# Self-Oscillating_Converter.net
KiCad netlist of a schematic drawn in Altium Designer
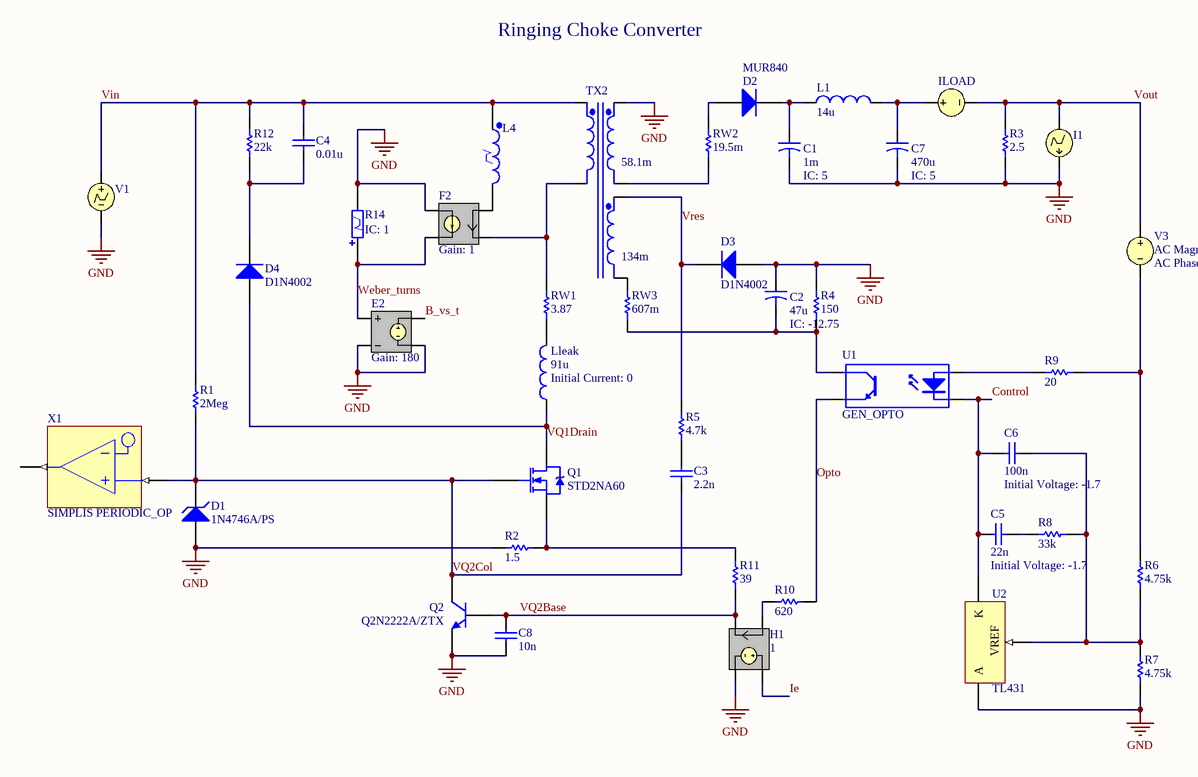
[diagram p0: Self-Oscillating Converter.SchDoc]

(export (version "E")
  (design (tool "Eeschema 10.0.6"))
  (components
    (comp (ref "C1")
      (value "Cap Elec (L1-3)")
      (footprint "CAPR5-4X5")
      (description "Electrolytic Capacitor (Levels 1-3)")
      (fields (field (name "IC") "5") (field (name "CC") "1m") (field (name "PUBLISHER") "Altium Limited"))
      (libsource (lib "SIMetrix Devices") (part "Cap Elec (L1-3)"))
    )
    (comp (ref "C2")
      (value "Cap Elec (L1-3)")
      (footprint "CAPR5-4X5")
      (description "Electrolytic Capacitor (Levels 1-3)")
      (fields
        (field (name "IC") "-12.75")
        (field (name "CC") "47u")
        (field (name "PUBLISHER") "Altium Limited")
      )
      (libsource (lib "SIMetrix Devices") (part "Cap Elec (L1-3)"))
    )
    (comp (ref "C3")
      (value "2.2n")
      (footprint "RAD-0.3")
      (description "Capacitor")
      (fields (field (name "Comment") "Cap") (field (name "PUBLISHER") "Altium Limited"))
      (libsource (lib "Miscellaneous Devices") (part "Cap"))
    )
    (comp (ref "C4")
      (value "0.01u")
      (footprint "RAD-0.3")
      (description "Capacitor")
      (fields (field (name "Comment") "Cap") (field (name "PUBLISHER") "Altium Limited"))
      (libsource (lib "Miscellaneous Devices") (part "Cap"))
    )
    (comp (ref "C5")
      (value "22n")
      (footprint "RAD-0.3")
      (description "Capacitor")
      (fields
        (field (name "INITIAL VOLTAGE") "-1.7")
        (field (name "Comment") "Cap")
        (field (name "PUBLISHER") "Altium Limited")
      )
      (libsource (lib "Miscellaneous Devices") (part "Cap"))
    )
    (comp (ref "C6")
      (value "100n")
      (footprint "RAD-0.3")
      (description "Capacitor")
      (fields
        (field (name "INITIAL VOLTAGE") "-1.7")
        (field (name "Comment") "Cap")
        (field (name "PUBLISHER") "Altium Limited")
      )
      (libsource (lib "Miscellaneous Devices") (part "Cap"))
    )
    (comp (ref "C7")
      (value "Cap Elec (L1-3)")
      (footprint "CAPR5-4X5")
      (description "Electrolytic Capacitor (Levels 1-3)")
      (fields (field (name "IC") "5") (field (name "CC") "470u") (field (name "PUBLISHER") "Altium Limited"))
      (libsource (lib "SIMetrix Devices") (part "Cap Elec (L1-3)"))
    )
    (comp (ref "C8")
      (value "10n")
      (footprint "RAD-0.3")
      (description "Capacitor")
      (fields (field (name "Comment") "Cap") (field (name "PUBLISHER") "Altium Limited"))
      (libsource (lib "Miscellaneous Devices") (part "Cap"))
    )
    (comp (ref "D1")
      (value "1N4746A/PS")
      (footprint "59-03")
      (description "One Watt Hermetically Sealed Glass Silicon Zener Diode")
      (fields (field (name "PUBLISHER") "Altium Limited"))
      (libsource (lib "SIMetrix Devices") (part "1N4746A/PS"))
    )
    (comp (ref "D2")
      (value "MUR840")
      (footprint "SMC")
      (description "Ultrafast Recovery Rectifier")
      (fields (field (name "PUBLISHER") "Altium Limited"))
      (libsource (lib "SIMetrix Devices") (part "MUR840"))
    )
    (comp (ref "D3")
      (value "D1N4002")
      (footprint "DO-41")
      (description "1 Amp General Purpose Rectifier")
      (fields (field (name "PUBLISHER") "Altium Limited"))
      (libsource (lib "SIMetrix Devices") (part "D1N4002"))
    )
    (comp (ref "D4")
      (value "D1N4002")
      (footprint "DO-41")
      (description "1 Amp General Purpose Rectifier")
      (fields (field (name "PUBLISHER") "Altium Limited"))
      (libsource (lib "SIMetrix Devices") (part "D1N4002"))
    )
    (comp (ref "E2")
      (value "ESRC")
      (description "Voltage Controlled Voltage Source")
      (fields (field (name "GAIN") "180") (field (name "PUBLISHER") "Altium Limited"))
      (libsource (lib "Simulation Sources") (part "ESRC"))
    )
    (comp (ref "F2")
      (value "FSRC")
      (description "Current Controlled Current Source")
      (fields (field (name "GAIN") "1") (field (name "PUBLISHER") "Altium Limited"))
      (libsource (lib "Simulation Sources") (part "FSRC"))
    )
    (comp (ref "H1")
      (value "HSRC")
      (description "Current Controlled Voltage Source")
      (fields (field (name "GAIN") "1") (field (name "PUBLISHER") "Altium Limited"))
      (libsource (lib "Simulation Sources") (part "HSRC"))
    )
    (comp (ref "I1")
      (value "IPWL")
      (description "Piecewise Linear Current Source")
      (fields (field (name "PUBLISHER") "Altium Limited"))
      (libsource (lib "Simulation Sources") (part "IPWL"))
    )
    (comp (ref "ILOAD")
      (value "VSRC")
      (description "Voltage Source")
      (fields (field (name "PUBLISHER") "Altium Limited"))
      (libsource (lib "Simulation Sources") (part "VSRC"))
    )
    (comp (ref "L1")
      (value "14u")
      (footprint "0402-A")
      (description "Lossy Inductor")
      (fields (field (name "PUBLISHER") "Altium Limited"))
      (libsource (lib "SIMetrix Devices") (part "Inductor (Lossy)"))
    )
    (comp (ref "L4")
      (value "SIMPLIS PWLL5")
      (description "Piecewise Linear Inductor (5-segment)")
      (fields (field (name "PUBLISHER") "Altium Limited"))
      (libsource (lib "SIMPLIS Devices") (part "SIMPLIS PWLL5"))
    )
    (comp (ref "Lleak")
      (value "91u")
      (footprint "0402-A")
      (description "Inductor")
      (fields (field (name "INITIAL CURRENT") "0") (field (name "PUBLISHER") "Altium Limited"))
      (libsource (lib "Miscellaneous Devices") (part "Inductor"))
    )
    (comp (ref "Q1")
      (value "STD2NA60")
      (footprint "TO-220AB")
      (description "N-Channel Enhancement Mode Power MOS Transistor")
      (fields (field (name "PUBLISHER") "Altium Limited"))
      (libsource (lib "SIMetrix Devices") (part "STD2NA60"))
    )
    (comp (ref "Q2")
      (value "Q2N2222A/ZTX")
      (footprint "TO-18")
      (description "Zetex General Purpose Transistor NPN Silicon")
      (fields (field (name "PUBLISHER") "Altium Limited"))
      (libsource (lib "SIMetrix Devices") (part "Q2N2222A/ZTX"))
    )
    (comp (ref "R1")
      (value "2Meg")
      (footprint "AXIAL-0.3")
      (description "Resistor")
      (fields (field (name "Comment") "Res1") (field (name "PUBLISHER") "Altium Limited"))
      (libsource (lib "Miscellaneous Devices") (part "Res1"))
    )
    (comp (ref "R2")
      (value "1.5")
      (footprint "AXIAL-0.3")
      (description "Resistor")
      (fields (field (name "Comment") "Res1") (field (name "PUBLISHER") "Altium Limited"))
      (libsource (lib "Miscellaneous Devices") (part "Res1"))
    )
    (comp (ref "R3")
      (value "2.5")
      (footprint "AXIAL-0.3")
      (description "Resistor")
      (fields (field (name "Comment") "Res1") (field (name "PUBLISHER") "Altium Limited"))
      (libsource (lib "Miscellaneous Devices") (part "Res1"))
    )
    (comp (ref "R4")
      (value "150")
      (footprint "AXIAL-0.3")
      (description "Resistor")
      (fields (field (name "Comment") "Res1") (field (name "PUBLISHER") "Altium Limited"))
      (libsource (lib "Miscellaneous Devices") (part "Res1"))
    )
    (comp (ref "R5")
      (value "4.7k")
      (footprint "AXIAL-0.3")
      (description "Resistor")
      (fields (field (name "Comment") "Res1") (field (name "PUBLISHER") "Altium Limited"))
      (libsource (lib "Miscellaneous Devices") (part "Res1"))
    )
    (comp (ref "R6")
      (value "4.75k")
      (footprint "AXIAL-0.3")
      (description "Resistor")
      (fields (field (name "Comment") "Res1") (field (name "PUBLISHER") "Altium Limited"))
      (libsource (lib "Miscellaneous Devices") (part "Res1"))
    )
    (comp (ref "R7")
      (value "4.75k")
      (footprint "AXIAL-0.3")
      (description "Resistor")
      (fields (field (name "Comment") "Res1") (field (name "PUBLISHER") "Altium Limited"))
      (libsource (lib "Miscellaneous Devices") (part "Res1"))
    )
    (comp (ref "R8")
      (value "33k")
      (footprint "AXIAL-0.3")
      (description "Resistor")
      (fields (field (name "Comment") "Res1") (field (name "PUBLISHER") "Altium Limited"))
      (libsource (lib "Miscellaneous Devices") (part "Res1"))
    )
    (comp (ref "R9")
      (value "20")
      (footprint "AXIAL-0.3")
      (description "Resistor")
      (fields (field (name "Comment") "Res1") (field (name "PUBLISHER") "Altium Limited"))
      (libsource (lib "Miscellaneous Devices") (part "Res1"))
    )
    (comp (ref "R10")
      (value "620")
      (footprint "AXIAL-0.3")
      (description "Resistor")
      (fields (field (name "Comment") "Res1") (field (name "PUBLISHER") "Altium Limited"))
      (libsource (lib "Miscellaneous Devices") (part "Res1"))
    )
    (comp (ref "R11")
      (value "39")
      (footprint "AXIAL-0.3")
      (description "Resistor")
      (fields (field (name "Comment") "Res1") (field (name "PUBLISHER") "Altium Limited"))
      (libsource (lib "Miscellaneous Devices") (part "Res1"))
    )
    (comp (ref "R12")
      (value "22k")
      (footprint "AXIAL-0.3")
      (description "Resistor")
      (fields (field (name "Comment") "Res1") (field (name "PUBLISHER") "Altium Limited"))
      (libsource (lib "Miscellaneous Devices") (part "Res1"))
    )
    (comp (ref "R14")
      (value "SIMPLIS VPWLR5")
      (description "Voltage-Controlled Piecewise Linear Resistor (5-segment)")
      (fields (field (name "IC") "1") (field (name "PUBLISHER") "Altium Limited"))
      (libsource (lib "SIMPLIS Devices") (part "SIMPLIS VPWLR5"))
    )
    (comp (ref "RW1")
      (value "3.87")
      (footprint "AXIAL-0.3")
      (description "Resistor")
      (fields (field (name "Comment") "Res1") (field (name "PUBLISHER") "Altium Limited"))
      (libsource (lib "Miscellaneous Devices") (part "Res1"))
    )
    (comp (ref "RW2")
      (value "19.5m")
      (footprint "AXIAL-0.3")
      (description "Resistor")
      (fields (field (name "Comment") "Res1") (field (name "PUBLISHER") "Altium Limited"))
      (libsource (lib "Miscellaneous Devices") (part "Res1"))
    )
    (comp (ref "RW3")
      (value "607m")
      (footprint "AXIAL-0.3")
      (description "Resistor")
      (fields (field (name "Comment") "Res1") (field (name "PUBLISHER") "Altium Limited"))
      (libsource (lib "Miscellaneous Devices") (part "Res1"))
    )
    (comp (ref "TX2")
      (value "Trans3 Ideal")
      (footprint "TRF_6")
      (description "Three-winding Transformer (Ideal)")
      (fields
        (field (name "RATIO1") "58.1m")
        (field (name "RATIO2") "134m")
        (field (name "PUBLISHER") "Altium Limited")
      )
      (libsource (lib "Miscellaneous Devices") (part "Trans3 Ideal"))
    )
    (comp (ref "U1")
      (value "GEN_OPTO")
      (footprint "DIP-4")
      (description "General-Purpose Optocoupler")
      (fields (field (name "PUBLISHER") "Altium Limited"))
      (libsource (lib "SIMetrix Devices") (part "GEN_OPTO"))
    )
    (comp (ref "U2")
      (value "TL431")
      (footprint "LP03")
      (description "Adjustable Precision Shunt Regulator")
      (fields (field (name "PUBLISHER") "Altium Limited"))
      (libsource (lib "SIMetrix Devices") (part "TL431"))
    )
    (comp (ref "V1")
      (value "VPWL")
      (description "Piecewise Linear Voltage Source")
      (fields (field (name "PUBLISHER") "Altium Limited"))
      (libsource (lib "Simulation Sources") (part "VPWL"))
    )
    (comp (ref "V3")
      (value "VSRC")
      (description "Voltage Source")
      (fields
        (field (name "AC MAGNITUDE") "1")
        (field (name "AC PHASE") "0")
        (field (name "PUBLISHER") "Altium Limited")
      )
      (libsource (lib "Simulation Sources") (part "VSRC"))
    )
    (comp (ref "X1")
      (value "SIMPLIS PERIODIC_OP")
      (description "Periodic Operating Point Analysis Trigger")
      (fields (field (name "PUBLISHER") "Altium Limited"))
      (libsource (lib "SIMPLIS Devices") (part "SIMPLIS PERIODIC_OP"))
    )
  )
  (nets
    (net (code "1") (name "/B_vs_t") (class "Default")
      (node (ref "E2") (pin "3") (pinfunction "N+_3") (pintype "passive"))
    )
    (net (code "2") (name "/Control") (class "Default")
      (node (ref "C5") (pin "2") (pinfunction "2_2") (pintype "passive"))
      (node (ref "C6") (pin "2") (pinfunction "2_2") (pintype "passive"))
      (node (ref "U1") (pin "2") (pinfunction "K_2") (pintype "passive"))
      (node (ref "U2") (pin "3") (pinfunction "K_3") (pintype "power_in"))
    )
    (net (code "3") (name "/Ie") (class "Default")
      (node (ref "H1") (pin "3") (pinfunction "N+_3") (pintype "passive"))
    )
    (net (code "4") (name "/Opto") (class "Default")
      (node (ref "R10") (pin "1") (pinfunction "1_1") (pintype "passive"))
      (node (ref "U1") (pin "3") (pinfunction "E_3") (pintype "passive"))
    )
    (net (code "5") (name "/VQ1Drain") (class "Default")
      (node (ref "D4") (pin "1") (pinfunction "A_1") (pintype "passive"))
      (node (ref "Lleak") (pin "1") (pinfunction "1_1") (pintype "passive"))
      (node (ref "Q1") (pin "2") (pinfunction "D_2") (pintype "passive"))
    )
    (net (code "6") (name "/VQ2Base") (class "Default")
      (node (ref "C8") (pin "1") (pinfunction "1_1") (pintype "passive"))
      (node (ref "H1") (pin "2") (pinfunction "NC-_2") (pintype "passive"))
      (node (ref "Q2") (pin "2") (pinfunction "B_2") (pintype "passive"))
      (node (ref "R11") (pin "1") (pinfunction "1_1") (pintype "passive"))
    )
    (net (code "7") (name "/VQ2Col") (class "Default")
      (node (ref "C3") (pin "1") (pinfunction "1_1") (pintype "passive"))
      (node (ref "D1") (pin "2") (pinfunction "K_2") (pintype "passive"))
      (node (ref "Q1") (pin "1") (pinfunction "G_1") (pintype "passive"))
      (node (ref "Q2") (pin "3") (pinfunction "C_3") (pintype "passive"))
      (node (ref "R1") (pin "2") (pinfunction "2_2") (pintype "passive"))
      (node (ref "X1") (pin "1") (pinfunction "IN_1") (pintype "input"))
    )
    (net (code "8") (name "/Vin") (class "Default")
      (node (ref "C4") (pin "1") (pinfunction "1_1") (pintype "passive"))
      (node (ref "L4") (pin "1") (pinfunction "1_1") (pintype "passive"))
      (node (ref "R1") (pin "1") (pinfunction "1_1") (pintype "passive"))
      (node (ref "R12") (pin "1") (pinfunction "1_1") (pintype "passive"))
      (node (ref "TX2") (pin "1") (pinfunction "Pri+_1") (pintype "passive"))
      (node (ref "V1") (pin "1") (pinfunction "1_1") (pintype "passive"))
    )
    (net (code "9") (name "/Vout") (class "Default")
      (node (ref "I1") (pin "1") (pinfunction "1_1") (pintype "passive"))
      (node (ref "ILOAD") (pin "2") (pinfunction "2_2") (pintype "passive"))
      (node (ref "R3") (pin "1") (pinfunction "1_1") (pintype "passive"))
      (node (ref "V3") (pin "1") (pinfunction "1_1") (pintype "passive"))
    )
    (net (code "10") (name "/Vres") (class "Default")
      (node (ref "D3") (pin "2") (pinfunction "K_2") (pintype "passive"))
      (node (ref "R5") (pin "1") (pinfunction "1_1") (pintype "passive"))
      (node (ref "TX2") (pin "5") (pinfunction "Sec2+_5") (pintype "passive"))
    )
    (net (code "11") (name "/Weber_turns") (class "Default")
      (node (ref "E2") (pin "1") (pinfunction "NC+_1") (pintype "passive"))
      (node (ref "F2") (pin "4") (pinfunction "N-_4") (pintype "passive"))
      (node (ref "R14") (pin "1") (pinfunction "1_1") (pintype "passive"))
    )
    (net (code "12") (name "GND") (class "Default")
      (node (ref "C1") (pin "2") (pinfunction "2_2") (pintype "passive"))
      (node (ref "C2") (pin "1") (pinfunction "1_1") (pintype "passive"))
      (node (ref "C7") (pin "2") (pinfunction "2_2") (pintype "passive"))
      (node (ref "C8") (pin "2") (pinfunction "2_2") (pintype "passive"))
      (node (ref "D1") (pin "1") (pinfunction "A_1") (pintype "passive"))
      (node (ref "D3") (pin "1") (pinfunction "A_1") (pintype "passive"))
      (node (ref "E2") (pin "2") (pinfunction "NC-_2") (pintype "passive"))
      (node (ref "E2") (pin "4") (pinfunction "N-_4") (pintype "passive"))
      (node (ref "F2") (pin "3") (pinfunction "N+_3") (pintype "passive"))
      (node (ref "H1") (pin "4") (pinfunction "N-_4") (pintype "passive"))
      (node (ref "I1") (pin "2") (pinfunction "2_2") (pintype "passive"))
      (node (ref "Q2") (pin "1") (pinfunction "E_1") (pintype "passive"))
      (node (ref "R14") (pin "2") (pinfunction "2_2") (pintype "passive"))
      (node (ref "R2") (pin "1") (pinfunction "1_1") (pintype "passive"))
      (node (ref "R3") (pin "2") (pinfunction "2_2") (pintype "passive"))
      (node (ref "R4") (pin "1") (pinfunction "1_1") (pintype "passive"))
      (node (ref "R7") (pin "1") (pinfunction "1_1") (pintype "passive"))
      (node (ref "TX2") (pin "3") (pinfunction "Sec1+_3") (pintype "passive"))
      (node (ref "U2") (pin "2") (pinfunction "A_2") (pintype "power_in"))
      (node (ref "V1") (pin "2") (pinfunction "2_2") (pintype "passive"))
    )
    (net (code "13") (name "Net-(C3-Pad2)") (class "Default")
      (node (ref "C3") (pin "2") (pinfunction "2_2") (pintype "passive"))
      (node (ref "R5") (pin "2") (pinfunction "2_2") (pintype "passive"))
    )
    (net (code "14") (name "Net-(C5-Pad1)") (class "Default")
      (node (ref "C5") (pin "1") (pinfunction "1_1") (pintype "passive"))
      (node (ref "R8") (pin "1") (pinfunction "1_1") (pintype "passive"))
    )
    (net (code "15") (name "Net-(C7-Pad1)") (class "Default")
      (node (ref "C7") (pin "1") (pinfunction "1_1") (pintype "passive"))
      (node (ref "ILOAD") (pin "1") (pinfunction "1_1") (pintype "passive"))
      (node (ref "L1") (pin "2") (pinfunction "2_2") (pintype "passive"))
    )
    (net (code "16") (name "Net-(D2-A)") (class "Default")
      (node (ref "D2") (pin "1") (pinfunction "A_1") (pintype "passive"))
      (node (ref "RW2") (pin "1") (pinfunction "1_1") (pintype "passive"))
    )
    (net (code "17") (name "Net-(D2-K)") (class "Default")
      (node (ref "C1") (pin "1") (pinfunction "1_1") (pintype "passive"))
      (node (ref "D2") (pin "2") (pinfunction "K_2") (pintype "passive"))
      (node (ref "L1") (pin "1") (pinfunction "1_1") (pintype "passive"))
    )
    (net (code "18") (name "Net-(D4-K)") (class "Default")
      (node (ref "C4") (pin "2") (pinfunction "2_2") (pintype "passive"))
      (node (ref "D4") (pin "2") (pinfunction "K_2") (pintype "passive"))
      (node (ref "R12") (pin "2") (pinfunction "2_2") (pintype "passive"))
    )
    (net (code "19") (name "Net-(F2-NC+)") (class "Default")
      (node (ref "F2") (pin "1") (pinfunction "NC+_1") (pintype "passive"))
      (node (ref "L4") (pin "2") (pinfunction "2_2") (pintype "passive"))
    )
    (net (code "20") (name "Net-(F2-NC-)") (class "Default")
      (node (ref "F2") (pin "2") (pinfunction "NC-_2") (pintype "passive"))
      (node (ref "RW1") (pin "1") (pinfunction "1_1") (pintype "passive"))
      (node (ref "TX2") (pin "2") (pinfunction "Pri-_2") (pintype "passive"))
    )
    (net (code "21") (name "Net-(H1-NC+)") (class "Default")
      (node (ref "H1") (pin "1") (pinfunction "NC+_1") (pintype "passive"))
      (node (ref "R10") (pin "2") (pinfunction "2_2") (pintype "passive"))
    )
    (net (code "22") (name "Net-(Lleak-Pad2)") (class "Default")
      (node (ref "Lleak") (pin "2") (pinfunction "2_2") (pintype "passive"))
      (node (ref "RW1") (pin "2") (pinfunction "2_2") (pintype "passive"))
    )
    (net (code "23") (name "Net-(Q1-S)") (class "Default")
      (node (ref "Q1") (pin "3") (pinfunction "S_3") (pintype "passive"))
      (node (ref "R11") (pin "2") (pinfunction "2_2") (pintype "passive"))
      (node (ref "R2") (pin "2") (pinfunction "2_2") (pintype "passive"))
    )
    (net (code "24") (name "Net-(R6-Pad2)") (class "Default")
      (node (ref "R6") (pin "2") (pinfunction "2_2") (pintype "passive"))
      (node (ref "R9") (pin "2") (pinfunction "2_2") (pintype "passive"))
      (node (ref "V3") (pin "2") (pinfunction "2_2") (pintype "passive"))
    )
    (net (code "25") (name "Net-(TX2-Sec1-)") (class "Default")
      (node (ref "RW2") (pin "2") (pinfunction "2_2") (pintype "passive"))
      (node (ref "TX2") (pin "4") (pinfunction "Sec1-_4") (pintype "passive"))
    )
    (net (code "26") (name "Net-(TX2-Sec2-)") (class "Default")
      (node (ref "RW3") (pin "1") (pinfunction "1_1") (pintype "passive"))
      (node (ref "TX2") (pin "6") (pinfunction "Sec2-_6") (pintype "passive"))
    )
    (net (code "27") (name "Net-(U1-A)") (class "Default")
      (node (ref "R9") (pin "1") (pinfunction "1_1") (pintype "passive"))
      (node (ref "U1") (pin "1") (pinfunction "A_1") (pintype "passive"))
    )
    (net (code "28") (name "Net-(U1-C)") (class "Default")
      (node (ref "C2") (pin "2") (pinfunction "2_2") (pintype "passive"))
      (node (ref "R4") (pin "2") (pinfunction "2_2") (pintype "passive"))
      (node (ref "RW3") (pin "2") (pinfunction "2_2") (pintype "passive"))
      (node (ref "U1") (pin "4") (pinfunction "C_4") (pintype "passive"))
    )
    (net (code "29") (name "Net-(U2-VREF)") (class "Default")
      (node (ref "C6") (pin "1") (pinfunction "1_1") (pintype "passive"))
      (node (ref "R6") (pin "1") (pinfunction "1_1") (pintype "passive"))
      (node (ref "R7") (pin "2") (pinfunction "2_2") (pintype "passive"))
      (node (ref "R8") (pin "2") (pinfunction "2_2") (pintype "passive"))
      (node (ref "U2") (pin "1") (pinfunction "VREF_1") (pintype "input"))
    )
    (net (code "30") (name "unconnected-(X1-OUT-Pad3)") (class "Default")
      (node (ref "X1") (pin "3") (pinfunction "OUT_3") (pintype "output"))
    )
  )
)
